# NMX-200.net
KiCad netlist of a schematic drawn in EAGLE
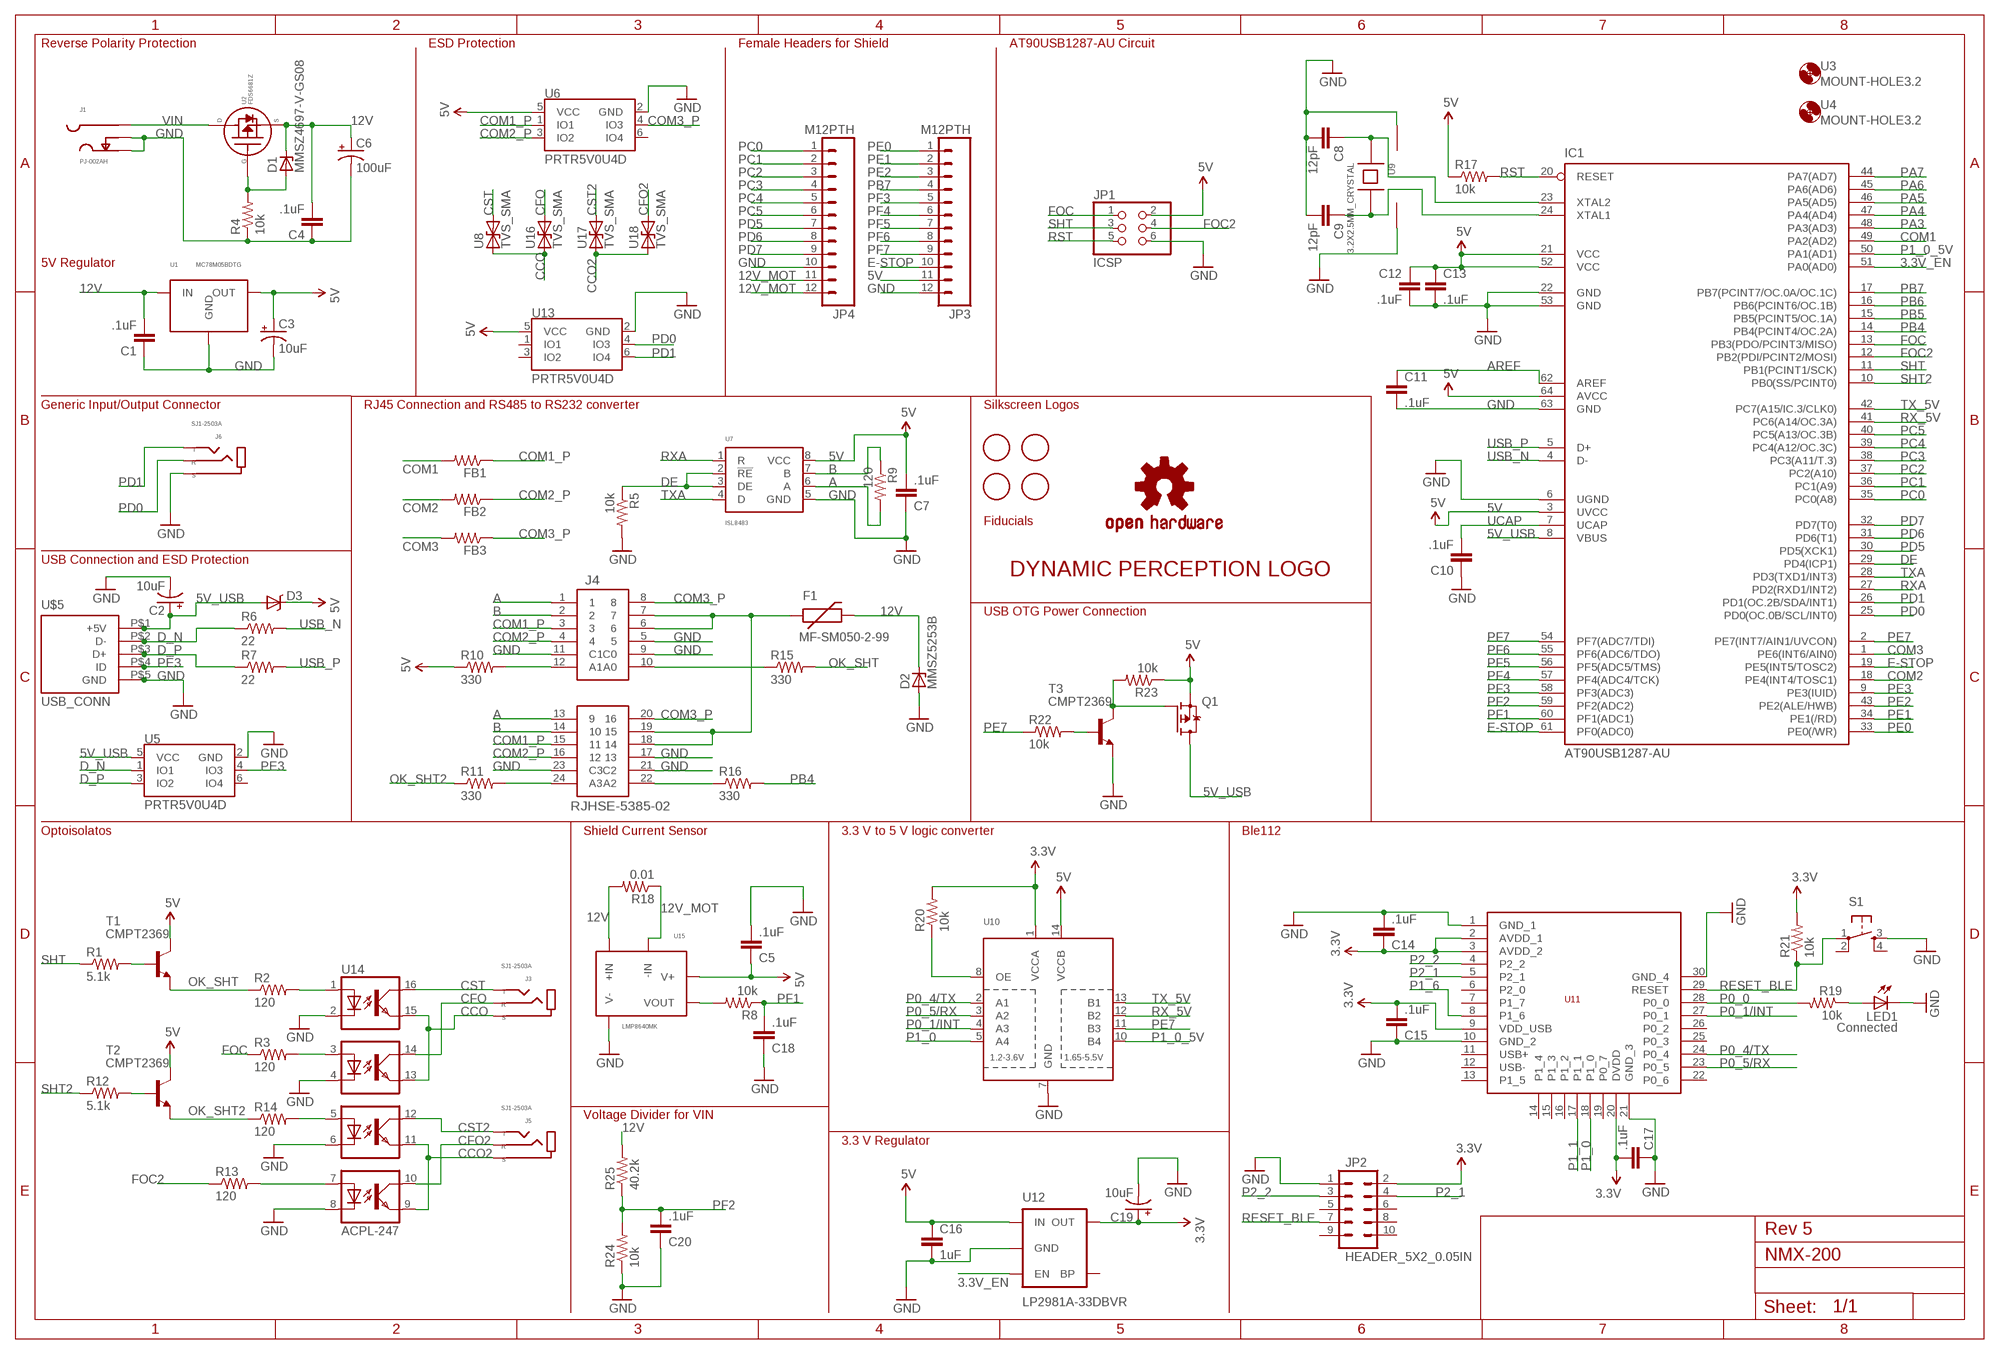
[diagram p0: schematic, sheet 1]

(export (version "E")
  (design (tool "Eeschema 10.0.6"))
  (components
    (comp (ref "C1")
      (value ".1uF")
      (footprint "eagle-import:0402-CAP")
      (fields (field (name "MF") "Taiyo Yuden") (field (name "MPN") "TMK105BJ104KV-F"))
      (libsource (lib "eagle-import") (part "CAP0402-CAP"))
    )
    (comp (ref "C2")
      (value "10uF")
      (footprint "eagle-import:EIA3216")
      (fields (field (name "MF") "Kemet") (field (name "MPN") "T491A106M016AT"))
      (libsource (lib "eagle-import") (part "CAP_POL1206"))
    )
    (comp (ref "C3")
      (value "10uF")
      (footprint "eagle-import:EIA3216")
      (fields (field (name "MF") "Kemet") (field (name "MPN") "T491A106M016AT"))
      (libsource (lib "eagle-import") (part "CAP_POL1206"))
    )
    (comp (ref "C4")
      (value ".1uF")
      (footprint "eagle-import:0402-CAP")
      (fields (field (name "MF") "Taiyo Yuden") (field (name "MPN") "TMK105BJ104KV-F"))
      (libsource (lib "eagle-import") (part "CAP0402-CAP"))
    )
    (comp (ref "C5")
      (value ".1uF")
      (footprint "eagle-import:0402-CAP")
      (fields (field (name "MF") "Taiyo Yuden") (field (name "MPN") "TMK105BJ104KV-F"))
      (libsource (lib "eagle-import") (part "CAP0402-CAP"))
    )
    (comp (ref "C6")
      (value "100uF")
      (footprint "eagle-import:PANASONIC_D")
      (fields (field (name "MF") "Panasonic Electronic Components") (field (name "MPN") "EEE-1EA101XP"))
      (libsource (lib "eagle-import") (part "CAP_POLD"))
    )
    (comp (ref "C7")
      (value ".1uF")
      (footprint "eagle-import:0402-CAP")
      (fields (field (name "MF") "Taiyo Yuden") (field (name "MPN") "TMK105BJ104KV-F"))
      (libsource (lib "eagle-import") (part "CAP0402-CAP"))
    )
    (comp (ref "C8")
      (value "12pF")
      (footprint "eagle-import:0402-CAP")
      (fields (field (name "MF") "TDK Corporation") (field (name "MPN") "C1005C0G1H120J050BA"))
      (libsource (lib "eagle-import") (part "CAP0402-CAP"))
    )
    (comp (ref "C9")
      (value "12pF")
      (footprint "eagle-import:0402-CAP")
      (fields (field (name "MF") "TDK Corporation") (field (name "MPN") "C1005C0G1H120J050BA"))
      (libsource (lib "eagle-import") (part "CAP0402-CAP"))
    )
    (comp (ref "C10")
      (value ".1uF")
      (footprint "eagle-import:0402-CAP")
      (fields (field (name "MF") "Taiyo Yuden") (field (name "MPN") "TMK105BJ104KV-F"))
      (libsource (lib "eagle-import") (part "CAP0402-CAP"))
    )
    (comp (ref "C11")
      (value ".1uF")
      (footprint "eagle-import:0402-CAP")
      (fields (field (name "MF") "Taiyo Yuden") (field (name "MPN") "TMK105BJ104KV-F"))
      (libsource (lib "eagle-import") (part "CAP0402-CAP"))
    )
    (comp (ref "C12")
      (value ".1uF")
      (footprint "eagle-import:0402-CAP")
      (fields (field (name "MF") "Taiyo Yuden") (field (name "MPN") "TMK105BJ104KV-F"))
      (libsource (lib "eagle-import") (part "CAP0402-CAP"))
    )
    (comp (ref "C13")
      (value ".1uF")
      (footprint "eagle-import:0402-CAP")
      (fields (field (name "MF") "Taiyo Yuden") (field (name "MPN") "TMK105BJ104KV-F"))
      (libsource (lib "eagle-import") (part "CAP0402-CAP"))
    )
    (comp (ref "C14")
      (value ".1uF")
      (footprint "eagle-import:0402-CAP")
      (fields (field (name "MF") "Taiyo Yuden") (field (name "MPN") "TMK105BJ104KV-F"))
      (libsource (lib "eagle-import") (part "CAP0402-CAP"))
    )
    (comp (ref "C15")
      (value ".1uF")
      (footprint "eagle-import:0402-CAP")
      (fields (field (name "MF") "Taiyo Yuden") (field (name "MPN") "TMK105BJ104KV-F"))
      (libsource (lib "eagle-import") (part "CAP0402-CAP"))
    )
    (comp (ref "C16")
      (value "1uF")
      (footprint "eagle-import:0402-CAP")
      (fields (field (name "MF") "TDK Corporation") (field (name "MPN") "C1005X5R1C105K050BC"))
      (libsource (lib "eagle-import") (part "CAP0402-CAP"))
    )
    (comp (ref "C17")
      (value ".1uF")
      (footprint "eagle-import:0402-CAP")
      (fields (field (name "MF") "Taiyo Yuden") (field (name "MPN") "TMK105BJ104KV-F"))
      (libsource (lib "eagle-import") (part "CAP0402-CAP"))
    )
    (comp (ref "C18")
      (value ".1uF")
      (footprint "eagle-import:0402-CAP")
      (fields (field (name "MF") "Taiyo Yuden") (field (name "MPN") "TMK105BJ104KV-F"))
      (libsource (lib "eagle-import") (part "CAP0402-CAP"))
    )
    (comp (ref "C19")
      (value "10uF")
      (footprint "eagle-import:EIA3216")
      (fields (field (name "MF") "Kemet") (field (name "MPN") "T491A106M016AT"))
      (libsource (lib "eagle-import") (part "CAP_POL1206"))
    )
    (comp (ref "C20")
      (value ".1uF")
      (footprint "eagle-import:0402-CAP")
      (fields (field (name "MF") "Taiyo Yuden") (field (name "MPN") "TMK105BJ104KV-F"))
      (libsource (lib "eagle-import") (part "CAP0402-CAP"))
    )
    (comp (ref "D1")
      (value "MMSZ4697-V-GS08")
      (footprint "eagle-import:SOD123")
      (fields
        (field (name "MF") "Vishay Semiconductor Diodes Division")
        (field (name "MPN") "MMSZ4697-E3-08")
      )
      (libsource (lib "eagle-import") (part "ZENER-DIODESOD123"))
    )
    (comp (ref "D2")
      (value "MMSZ5253B")
      (footprint "eagle-import:SOD123")
      (fields (field (name "MF") "Fairchild Semiconductor"))
      (libsource (lib "eagle-import") (part "ZENER-DIODESOD123"))
    )
    (comp (ref "D3")
      (value "DIODE-SCHOTTKY-BAT20J")
      (footprint "eagle-import:SOD-323")
      (fields (field (name "MF") "NXP Semiconductors") (field (name "MPN") "PMEG3010BEA,115"))
      (libsource (lib "eagle-import") (part "DIODE-SCHOTTKY-BAT20J"))
    )
    (comp (ref "F1")
      (value "MF-SM050-2-99")
      (footprint "eagle-import:PTC-2920")
      (fields (field (name "MF") "Bel Fuse") (field (name "MPN") "0ZCD0050FF2C"))
      (libsource (lib "eagle-import") (part "PTC2920"))
    )
    (comp (ref "FB1")
      (value "HZ0402B102R-10")
      (footprint "eagle-import:R0402")
      (fields (field (name "MF") "Laird-Signal Integrity Products"))
      (libsource (lib "eagle-import") (part "R-US_R0402"))
    )
    (comp (ref "FB2")
      (value "HZ0402B102R-10")
      (footprint "eagle-import:R0402")
      (fields (field (name "MF") "Laird-Signal Integrity Products"))
      (libsource (lib "eagle-import") (part "R-US_R0402"))
    )
    (comp (ref "FB3")
      (value "HZ0402B102R-10")
      (footprint "eagle-import:R0402")
      (fields (field (name "MF") "Laird-Signal Integrity Products"))
      (libsource (lib "eagle-import") (part "R-US_R0402"))
    )
    (comp (ref "FRAME2")
      (value "A3L-LOCSILK_SCREEN")
      (footprint "eagle-import:DRAWING_NAME")
      (libsource (lib "eagle-import") (part "A3L-LOCSILK_SCREEN"))
    )
    (comp (ref "IC1")
      (value "AT90USB1287-AU")
      (footprint "eagle-import:TQFP64")
      (fields (field (name "MF") "Atmel"))
      (libsource (lib "eagle-import") (part "AT90USB1287-AU"))
    )
    (comp (ref "J1")
      (value "PJ-002AH")
      (footprint "eagle-import:DC_JACK_KLDX")
      (fields (field (name "MF") "CUI Inc"))
      (libsource (lib "eagle-import") (part "DC_JACK"))
    )
    (comp (ref "J3")
      (value "SJ1-2503A")
      (footprint "eagle-import:SJ1-2503A")
      (fields (field (name "MF") "CUI Inc"))
      (libsource (lib "eagle-import") (part "TRS_JACKSJ1-2503A"))
    )
    (comp (ref "J4")
      (value "RJHSE-5385-02")
      (footprint "eagle-import:RJHSE-5385-02")
      (fields (field (name "MF") "Amphenol Commercial Products"))
      (libsource (lib "eagle-import") (part "RJ45_DOUBLEPTH"))
    )
    (comp (ref "J5")
      (value "SJ1-2503A")
      (footprint "eagle-import:SJ1-2503A")
      (fields (field (name "MF") "CUI Inc"))
      (libsource (lib "eagle-import") (part "TRS_JACKSJ1-2503A"))
    )
    (comp (ref "J6")
      (value "SJ1-2503A")
      (footprint "eagle-import:SJ1-2503A")
      (fields (field (name "MF") "CUI Inc"))
      (libsource (lib "eagle-import") (part "TRS_JACKSJ1-2503A"))
    )
    (comp (ref "JP1")
      (value "ICSP")
      (footprint "eagle-import:2X03")
      (fields (field (name "MF") "FCI") (field (name "MPN") "67996-406HLF"))
      (libsource (lib "eagle-import") (part "PINHD-2X3"))
    )
    (comp (ref "JP2")
      (value "HEADER_5X2_0.05IN")
      (footprint "eagle-import:HEADER_5X2_0.05IN")
      (fields (field (name "MF") "FCI") (field (name "MPN") "20021121-00010T4LF"))
      (libsource (lib "eagle-import") (part "HEADER_5X2_0.05IN"))
    )
    (comp (ref "JP3")
      (value "M12PTH")
      (footprint "eagle-import:1X12")
      (fields (field (name "MF") "Sullins Connector Solutions") (field (name "MPN") "PPTC121LFBN-RC"))
      (libsource (lib "eagle-import") (part "M12PTH"))
    )
    (comp (ref "JP4")
      (value "M12PTH")
      (footprint "eagle-import:1X12")
      (fields (field (name "MF") "Sullins Connector Solutions") (field (name "MPN") "PPTC121LFBN-RC"))
      (libsource (lib "eagle-import") (part "M12PTH"))
    )
    (comp (ref "LED1")
      (value "Connected")
      (footprint "eagle-import:LED-0603")
      (fields (field (name "MF") "Lite-On Inc") (field (name "MPN") "LTST-S270TBKT"))
      (libsource (lib "eagle-import") (part "LED0603"))
    )
    (comp (ref "Q1")
      (value "P-CHANNEL_MOSFET")
      (footprint "eagle-import:SOT23-3")
      (fields (field (name "MF") "Fairchild Semiconductor") (field (name "MPN") "FDV304P"))
      (libsource (lib "eagle-import") (part "P-CHANNEL_MOSFET"))
    )
    (comp (ref "R1")
      (value "5.1k")
      (footprint "eagle-import:R0402")
      (fields (field (name "MF") "Yageo") (field (name "MPN") "RC0402JR-075K1L"))
      (libsource (lib "eagle-import") (part "R-US_R0402"))
    )
    (comp (ref "R2")
      (value "120")
      (footprint "eagle-import:R0402")
      (fields (field (name "MF") "Yageo") (field (name "MPN") "RC0402FR-07180RL"))
      (libsource (lib "eagle-import") (part "R-US_R0402"))
    )
    (comp (ref "R3")
      (value "120")
      (footprint "eagle-import:R0402")
      (fields (field (name "MF") "Yageo") (field (name "MPN") "RC0402FR-07180RL"))
      (libsource (lib "eagle-import") (part "R-US_R0402"))
    )
    (comp (ref "R4")
      (value "10k")
      (footprint "eagle-import:R0402")
      (fields (field (name "MF") "Yageo") (field (name "MPN") "RC0402FR-0710KL"))
      (libsource (lib "eagle-import") (part "R-US_R0402"))
    )
    (comp (ref "R5")
      (value "10k")
      (footprint "eagle-import:R0402")
      (fields (field (name "MF") "Yageo") (field (name "MPN") "RC0402FR-0710KL"))
      (libsource (lib "eagle-import") (part "R-US_R0402"))
    )
    (comp (ref "R6")
      (value "22")
      (footprint "eagle-import:R0402")
      (fields (field (name "MF") "Yageo") (field (name "MPN") "RC0402JR-0722RL"))
      (libsource (lib "eagle-import") (part "R-US_R0402"))
    )
    (comp (ref "R7")
      (value "22")
      (footprint "eagle-import:R0402")
      (fields (field (name "MF") "Yageo") (field (name "MPN") "RC0402JR-0722RL"))
      (libsource (lib "eagle-import") (part "R-US_R0402"))
    )
    (comp (ref "R8")
      (value "10k")
      (footprint "eagle-import:R0402")
      (fields (field (name "MF") "Yageo") (field (name "MPN") "RC0402FR-0710KL"))
      (libsource (lib "eagle-import") (part "R-US_R0402"))
    )
    (comp (ref "R9")
      (value "120")
      (footprint "eagle-import:R0402")
      (fields (field (name "MF") "Yageo") (field (name "MPN") "RC0402JR-07120RL"))
      (libsource (lib "eagle-import") (part "R-US_R0402"))
    )
    (comp (ref "R10")
      (value "330")
      (footprint "eagle-import:R0402")
      (fields (field (name "MF") "Yageo") (field (name "MPN") "RC0402FR-07330RL"))
      (libsource (lib "eagle-import") (part "R-US_R0402"))
    )
    (comp (ref "R11")
      (value "330")
      (footprint "eagle-import:R0402")
      (fields (field (name "MF") "Yageo") (field (name "MPN") "RC0402FR-07330RL"))
      (libsource (lib "eagle-import") (part "R-US_R0402"))
    )
    (comp (ref "R12")
      (value "5.1k")
      (footprint "eagle-import:R0402")
      (fields (field (name "MF") "Yageo") (field (name "MPN") "RC0402JR-075K1L"))
      (libsource (lib "eagle-import") (part "R-US_R0402"))
    )
    (comp (ref "R13")
      (value "120")
      (footprint "eagle-import:R0402")
      (fields (field (name "MF") "Yageo") (field (name "MPN") "RC0402FR-07180RL"))
      (libsource (lib "eagle-import") (part "R-US_R0402"))
    )
    (comp (ref "R14")
      (value "120")
      (footprint "eagle-import:R0402")
      (fields (field (name "MF") "Yageo") (field (name "MPN") "RC0402FR-07180RL"))
      (libsource (lib "eagle-import") (part "R-US_R0402"))
    )
    (comp (ref "R15")
      (value "330")
      (footprint "eagle-import:R0402")
      (fields (field (name "MF") "Yageo") (field (name "MPN") "RC0402FR-07330RL"))
      (libsource (lib "eagle-import") (part "R-US_R0402"))
    )
    (comp (ref "R16")
      (value "330")
      (footprint "eagle-import:R0402")
      (fields (field (name "MF") "Yageo") (field (name "MPN") "RC0402FR-07330RL"))
      (libsource (lib "eagle-import") (part "R-US_R0402"))
    )
    (comp (ref "R17")
      (value "10k")
      (footprint "eagle-import:R0402")
      (fields (field (name "MF") "Yageo") (field (name "MPN") "RC0402FR-0710KL"))
      (libsource (lib "eagle-import") (part "R-US_R0402"))
    )
    (comp (ref "R18")
      (value "0.01")
      (footprint "eagle-import:R1206")
      (fields (field (name "MF") "TE Connectivity") (field (name "MPN") "RLP73V2BR010JTD"))
      (libsource (lib "eagle-import") (part "R-US_R1206"))
    )
    (comp (ref "R19")
      (value "10k")
      (footprint "eagle-import:R0402")
      (fields (field (name "MF") "Yageo") (field (name "MPN") "RC0402FR-0714KL"))
      (libsource (lib "eagle-import") (part "R-US_R0402"))
    )
    (comp (ref "R20")
      (value "10k")
      (footprint "eagle-import:R0402")
      (fields (field (name "MF") "Yageo") (field (name "MPN") "RC0402FR-0710KL"))
      (libsource (lib "eagle-import") (part "R-US_R0402"))
    )
    (comp (ref "R21")
      (value "10k")
      (footprint "eagle-import:R0402")
      (fields (field (name "MF") "Yageo") (field (name "MPN") "RC0402FR-0710KL"))
      (libsource (lib "eagle-import") (part "R-US_R0402"))
    )
    (comp (ref "R22")
      (value "10k")
      (footprint "eagle-import:R0402")
      (fields (field (name "MF") "Yageo") (field (name "MPN") "RC0402FR-0710KL"))
      (libsource (lib "eagle-import") (part "R-US_R0402"))
    )
    (comp (ref "R23")
      (value "10k")
      (footprint "eagle-import:R0402")
      (fields (field (name "MF") "Yageo") (field (name "MPN") "RC0402FR-0710KL"))
      (libsource (lib "eagle-import") (part "R-US_R0402"))
    )
    (comp (ref "R24")
      (value "10k")
      (footprint "eagle-import:R0402")
      (fields (field (name "MF") "Yageo") (field (name "MPN") "RC0402FR-0710KL"))
      (libsource (lib "eagle-import") (part "R-US_R0402"))
    )
    (comp (ref "R25")
      (value "40.2k")
      (footprint "eagle-import:R0402")
      (fields (field (name "MF") "Yageo") (field (name "MPN") "RC0402FR-0740K2L"))
      (libsource (lib "eagle-import") (part "R-US_R0402"))
    )
    (comp (ref "S1")
      (value "TAC_SWITCH")
      (footprint "eagle-import:TACTICLE_SWITCH_SMD_EVQP0_BOT")
      (fields (field (name "MF") "Panasonic Electronic Components") (field (name "MPN") "EVQ-P0Q02Q"))
      (libsource (lib "eagle-import") (part "TAC_SWITCH"))
    )
    (comp (ref "T1")
      (value "CMPT2369")
      (footprint "eagle-import:SOT23-BEC")
      (fields (field (name "MF") "Rohm Semiconductor") (field (name "MPN") "2SD1757KT146Q"))
      (libsource (lib "eagle-import") (part "-NPN-SOT23-BECBCW60"))
    )
    (comp (ref "T2")
      (value "CMPT2369")
      (footprint "eagle-import:SOT23-BEC")
      (fields (field (name "MF") "Rohm Semiconductor") (field (name "MPN") "2SD1757KT146Q"))
      (libsource (lib "eagle-import") (part "-NPN-SOT23-BECBCW60"))
    )
    (comp (ref "T3")
      (value "CMPT2369")
      (footprint "eagle-import:SOT23-BEC")
      (fields (field (name "MF") "Fairchild Semiconductor") (field (name "MPN") "BC847BMTF"))
      (libsource (lib "eagle-import") (part "-NPN-SOT23-BECBCW60"))
    )
    (comp (ref "U$1")
      (value "DP_LOGOMICRO")
      (footprint "eagle-import:DP_LOGO_MICRO")
      (libsource (lib "eagle-import") (part "DP_LOGOMICRO"))
    )
    (comp (ref "U$2")
      (value "OSHW-LOGOS")
      (footprint "eagle-import:OSHW-LOGO-S")
      (libsource (lib "eagle-import") (part "OSHW-LOGOS"))
    )
    (comp (ref "U$3")
      (value "FIDUCIAL")
      (footprint "eagle-import:FIDUCIAL_1MM")
      (libsource (lib "eagle-import") (part "FIDUCIAL"))
    )
    (comp (ref "U$4")
      (value "FIDUCIAL")
      (footprint "eagle-import:FIDUCIAL_1MM")
      (libsource (lib "eagle-import") (part "FIDUCIAL"))
    )
    (comp (ref "U$5")
      (value "USB_CONN")
      (footprint "eagle-import:10118194-0001LF")
      (libsource (lib "eagle-import") (part "USB_CONN"))
    )
    (comp (ref "U$6")
      (value "FIDUCIAL")
      (footprint "eagle-import:FIDUCIAL_1MM")
      (libsource (lib "eagle-import") (part "FIDUCIAL"))
    )
    (comp (ref "U$7")
      (value "FIDUCIAL")
      (footprint "eagle-import:FIDUCIAL_1MM")
      (libsource (lib "eagle-import") (part "FIDUCIAL"))
    )
    (comp (ref "U1")
      (value "MC78M05BDTG")
      (footprint "eagle-import:DPAK-3")
      (fields (field (name "MF") "ON Semiconductor") (field (name "MPN") "MC78M05BDTRKG"))
      (libsource (lib "eagle-import") (part "VOLTAGE_REG"))
    )
    (comp (ref "U2")
      (value "FDS6681Z")
      (footprint "eagle-import:DSO-8")
      (fields (field (name "MF") "Fairchild Semiconductor"))
      (libsource (lib "eagle-import") (part "MOSFET_P-CHANNEL"))
    )
    (comp (ref "U3")
      (value "MOUNT-HOLE3.2")
      (footprint "eagle-import:3,2")
      (libsource (lib "eagle-import") (part "MOUNT-HOLE3.2"))
    )
    (comp (ref "U4")
      (value "MOUNT-HOLE3.2")
      (footprint "eagle-import:3,2")
      (libsource (lib "eagle-import") (part "MOUNT-HOLE3.2"))
    )
    (comp (ref "U5")
      (value "PRTR5V0U4D")
      (footprint "eagle-import:SOT23-6")
      (fields (field (name "MF") "NXP Semiconductors"))
      (libsource (lib "eagle-import") (part "PRTR5V0U4D"))
    )
    (comp (ref "U6")
      (value "PRTR5V0U4D")
      (footprint "eagle-import:SOT23-6")
      (fields (field (name "MF") "NXP Semiconductors"))
      (libsource (lib "eagle-import") (part "PRTR5V0U4D"))
    )
    (comp (ref "U7")
      (value "ISL8483")
      (footprint "eagle-import:SO-08")
      (fields
        (field (name "MF") "TEXAS INSTRUMENTS")
        (field (name "MPN") "SN65176BD")
        (field (name "MF_1") "TEXAS INSTRUMENTS")
        (field (name "MPN_1") "SN65176BD")
        (field (name "OC_FARNELL") "9589970")
        (field (name "OC_NEWARK") "08F5891")
      )
      (libsource (lib "eagle-import") (part "SN65176D"))
    )
    (comp (ref "U8")
      (value "TVS_SMA")
      (footprint "eagle-import:SMA_DIODE")
      (fields (field (name "MF") "Bourns Inc") (field (name "MPN") "SMAJ48CA"))
      (libsource (lib "eagle-import") (part "TVS_SMA"))
    )
    (comp (ref "U9")
      (value "3.2X2.5MM_CRYSTAL")
      (footprint "eagle-import:3.2X2.5MM")
      (fields (field (name "MF") "AVX Corp/Kyocera Corp") (field (name "MPN") "CX3225SB16000E0FPZ25"))
      (libsource (lib "eagle-import") (part "3.2X2.5MM_CRYSTAL"))
    )
    (comp (ref "U10")
      (value "TXB0104PWR")
      (footprint "eagle-import:TSSOP14")
      (fields (field (name "MF") "Texas Instruments"))
      (libsource (lib "eagle-import") (part "TXB0104PWR"))
    )
    (comp (ref "U11")
      (value "BLE112")
      (footprint "eagle-import:BLE112-A")
      (fields (field (name "MF") "BlueGiga Technologies Inc") (field (name "MPN") "BLE112-A-V1"))
      (libsource (lib "eagle-import") (part "BLE112"))
    )
    (comp (ref "U12")
      (value "LP2981A-33DBVR")
      (footprint "eagle-import:SOT23-5")
      (fields (field (name "MF") "Texas Instruments"))
      (libsource (lib "eagle-import") (part "V_REG_LDOSMD"))
    )
    (comp (ref "U13")
      (value "PRTR5V0U4D")
      (footprint "eagle-import:SOT23-6")
      (fields (field (name "MF") "NXP Semiconductors"))
      (libsource (lib "eagle-import") (part "PRTR5V0U4D"))
    )
    (comp (ref "U14")
      (value "ACPL-247")
      (footprint "eagle-import:16-SOIC")
      (fields (field (name "MF") "Avago Technologies US Inc.") (field (name "MPN") "ACPL-247-500E"))
      (libsource (lib "eagle-import") (part "ACPL-247"))
    )
    (comp (ref "U15")
      (value "LMP8640MK")
      (footprint "eagle-import:6-SOT")
      (fields (field (name "MF") "Texas Instruments") (field (name "MPN") "LMP8640MK-H/NOPB"))
      (libsource (lib "eagle-import") (part "LMP8640MK"))
    )
    (comp (ref "U16")
      (value "TVS_SMA")
      (footprint "eagle-import:SMA_DIODE")
      (fields (field (name "MF") "Bourns Inc") (field (name "MPN") "SMAJ48CA"))
      (libsource (lib "eagle-import") (part "TVS_SMA"))
    )
    (comp (ref "U17")
      (value "TVS_SMA")
      (footprint "eagle-import:SMA_DIODE")
      (fields (field (name "MF") "Bourns Inc") (field (name "MPN") "SMAJ48CA"))
      (libsource (lib "eagle-import") (part "TVS_SMA"))
    )
    (comp (ref "U18")
      (value "TVS_SMA")
      (footprint "eagle-import:SMA_DIODE")
      (fields (field (name "MF") "Bourns Inc") (field (name "MPN") "SMAJ48CA"))
      (libsource (lib "eagle-import") (part "TVS_SMA"))
    )
  )
  (nets
    (net (code "1") (name "/3.3V_EN") (class "Default")
      (node (ref "IC1") (pin "51") (pinfunction "PA0(AD0)_51") (pintype "bidirectional"))
      (node (ref "U12") (pin "3") (pinfunction "EN_3") (pintype "input"))
    )
    (net (code "2") (name "/5V_USB") (class "Default")
      (node (ref "C2") (pin "A") (pinfunction "+_A") (pintype "passive"))
      (node (ref "D3") (pin "A") (pinfunction "A_A") (pintype "passive"))
      (node (ref "IC1") (pin "8") (pinfunction "VBUS_8") (pintype "power_in"))
      (node (ref "Q1") (pin "D") (pinfunction "D_D") (pintype "passive"))
      (node (ref "U$5") (pin "P$1") (pinfunction "+5V_P$1") (pintype "bidirectional"))
      (node (ref "U5") (pin "5") (pinfunction "VCC_5") (pintype "power_in"))
    )
    (net (code "3") (name "/12V") (class "Default")
      (node (ref "C1") (pin "2") (pinfunction "2_2") (pintype "passive"))
      (node (ref "C4") (pin "2") (pinfunction "2_2") (pintype "passive"))
      (node (ref "C6") (pin "+") (pinfunction "+_+") (pintype "passive"))
      (node (ref "D1") (pin "C") (pinfunction "C_C") (pintype "passive"))
      (node (ref "D2") (pin "C") (pinfunction "C_C") (pintype "passive"))
      (node (ref "F1") (pin "P$2") (pinfunction "2_P$2") (pintype "bidirectional"))
      (node (ref "R18") (pin "2") (pinfunction "2_2") (pintype "passive"))
      (node (ref "R25") (pin "2") (pinfunction "2_2") (pintype "passive"))
      (node (ref "U1") (pin "1") (pinfunction "IN_1") (pintype "bidirectional"))
      (node (ref "U15") (pin "3") (pinfunction "+IN_3") (pintype "bidirectional"))
      (node (ref "U2") (pin "1") (pinfunction "SOURCE_1") (pintype "bidirectional"))
      (node (ref "U2") (pin "2") (pinfunction "SOURCE_2") (pintype "bidirectional"))
      (node (ref "U2") (pin "3") (pinfunction "SOURCE_3") (pintype "bidirectional"))
    )
    (net (code "4") (name "/12V_MOT") (class "Default")
      (node (ref "JP4") (pin "11") (pinfunction "11_11") (pintype "passive"))
      (node (ref "JP4") (pin "12") (pinfunction "12_12") (pintype "passive"))
      (node (ref "R18") (pin "1") (pinfunction "1_1") (pintype "passive"))
      (node (ref "U15") (pin "4") (pinfunction "-IN_4") (pintype "bidirectional"))
    )
    (net (code "5") (name "/A") (class "Default")
      (node (ref "J4") (pin "1") (pinfunction "1_1") (pintype "bidirectional"))
      (node (ref "J4") (pin "13") (pinfunction "9_13") (pintype "bidirectional"))
      (node (ref "R9") (pin "2") (pinfunction "2_2") (pintype "passive"))
      (node (ref "U7") (pin "6") (pinfunction "A_6") (pintype "input"))
    )
    (net (code "6") (name "/AREF") (class "Default")
      (node (ref "C11") (pin "1") (pinfunction "1_1") (pintype "passive"))
      (node (ref "IC1") (pin "62") (pinfunction "AREF_62") (pintype "bidirectional"))
    )
    (net (code "7") (name "/B") (class "Default")
      (node (ref "J4") (pin "14") (pinfunction "10_14") (pintype "bidirectional"))
      (node (ref "J4") (pin "2") (pinfunction "2_2") (pintype "bidirectional"))
      (node (ref "R9") (pin "1") (pinfunction "1_1") (pintype "passive"))
      (node (ref "U7") (pin "7") (pinfunction "B_7") (pintype "input"))
    )
    (net (code "8") (name "/CCO") (class "Default")
      (node (ref "J3") (pin "1") (pinfunction "S_1") (pintype "bidirectional"))
      (node (ref "U14") (pin "13") (pinfunction "13_13") (pintype "passive"))
      (node (ref "U14") (pin "15") (pinfunction "15_15") (pintype "passive"))
      (node (ref "U16") (pin "C") (pinfunction "1_C") (pintype "passive"))
      (node (ref "U8") (pin "C") (pinfunction "1_C") (pintype "passive"))
    )
    (net (code "9") (name "/CCO2") (class "Default")
      (node (ref "J5") (pin "1") (pinfunction "S_1") (pintype "bidirectional"))
      (node (ref "U14") (pin "11") (pinfunction "11_11") (pintype "passive"))
      (node (ref "U14") (pin "9") (pinfunction "9_9") (pintype "passive"))
      (node (ref "U17") (pin "C") (pinfunction "1_C") (pintype "passive"))
      (node (ref "U18") (pin "C") (pinfunction "1_C") (pintype "passive"))
    )
    (net (code "10") (name "/CFO") (class "Default")
      (node (ref "J3") (pin "4") (pinfunction "R_4") (pintype "bidirectional"))
      (node (ref "U14") (pin "14") (pinfunction "14_14") (pintype "passive"))
      (node (ref "U16") (pin "A") (pinfunction "2_A") (pintype "passive"))
    )
    (net (code "11") (name "/CFO2") (class "Default")
      (node (ref "J5") (pin "4") (pinfunction "R_4") (pintype "bidirectional"))
      (node (ref "U14") (pin "10") (pinfunction "10_10") (pintype "passive"))
      (node (ref "U18") (pin "A") (pinfunction "2_A") (pintype "passive"))
    )
    (net (code "12") (name "/COM1") (class "Default")
      (node (ref "FB1") (pin "2") (pinfunction "2_2") (pintype "passive"))
      (node (ref "IC1") (pin "49") (pinfunction "PA2(AD2)_49") (pintype "bidirectional"))
    )
    (net (code "13") (name "/COM1_P") (class "Default")
      (node (ref "FB1") (pin "1") (pinfunction "1_1") (pintype "passive"))
      (node (ref "J4") (pin "15") (pinfunction "11_15") (pintype "bidirectional"))
      (node (ref "J4") (pin "3") (pinfunction "3_3") (pintype "bidirectional"))
      (node (ref "U6") (pin "1") (pinfunction "IO1_1") (pintype "bidirectional"))
    )
    (net (code "14") (name "/COM2") (class "Default")
      (node (ref "FB2") (pin "2") (pinfunction "2_2") (pintype "passive"))
      (node (ref "IC1") (pin "18") (pinfunction "PE4(INT4/TOSC1)_18") (pintype "bidirectional"))
    )
    (net (code "15") (name "/COM2_P") (class "Default")
      (node (ref "FB2") (pin "1") (pinfunction "1_1") (pintype "passive"))
      (node (ref "J4") (pin "16") (pinfunction "12_16") (pintype "bidirectional"))
      (node (ref "J4") (pin "4") (pinfunction "4_4") (pintype "bidirectional"))
      (node (ref "U6") (pin "3") (pinfunction "IO2_3") (pintype "bidirectional"))
    )
    (net (code "16") (name "/COM3") (class "Default")
      (node (ref "FB3") (pin "2") (pinfunction "2_2") (pintype "passive"))
      (node (ref "IC1") (pin "1") (pinfunction "PE6(INT6/AIN0)_1") (pintype "bidirectional"))
    )
    (net (code "17") (name "/COM3_P") (class "Default")
      (node (ref "FB3") (pin "1") (pinfunction "1_1") (pintype "passive"))
      (node (ref "J4") (pin "20") (pinfunction "16_20") (pintype "bidirectional"))
      (node (ref "J4") (pin "8") (pinfunction "8_8") (pintype "bidirectional"))
      (node (ref "U6") (pin "4") (pinfunction "IO3_4") (pintype "bidirectional"))
    )
    (net (code "18") (name "/CST") (class "Default")
      (node (ref "J3") (pin "2") (pinfunction "T_2") (pintype "bidirectional"))
      (node (ref "J3") (pin "3") (pinfunction "T_3") (pintype "bidirectional"))
      (node (ref "U14") (pin "16") (pinfunction "16_16") (pintype "passive"))
      (node (ref "U8") (pin "A") (pinfunction "2_A") (pintype "passive"))
    )
    (net (code "19") (name "/CST2") (class "Default")
      (node (ref "J5") (pin "2") (pinfunction "T_2") (pintype "bidirectional"))
      (node (ref "J5") (pin "3") (pinfunction "T_3") (pintype "bidirectional"))
      (node (ref "U14") (pin "12") (pinfunction "12_12") (pintype "passive"))
      (node (ref "U17") (pin "A") (pinfunction "2_A") (pintype "passive"))
    )
    (net (code "20") (name "/DE") (class "Default")
      (node (ref "IC1") (pin "29") (pinfunction "PD4(ICP1)_29") (pintype "bidirectional"))
      (node (ref "R5") (pin "1") (pinfunction "1_1") (pintype "passive"))
      (node (ref "U7") (pin "2") (pinfunction "~{RE}_2") (pintype "input"))
      (node (ref "U7") (pin "3") (pinfunction "DE_3") (pintype "input"))
    )
    (net (code "21") (name "/D_N") (class "Default")
      (node (ref "R6") (pin "1") (pinfunction "1_1") (pintype "passive"))
      (node (ref "U$5") (pin "P$2") (pinfunction "D-_P$2") (pintype "bidirectional"))
      (node (ref "U5") (pin "1") (pinfunction "IO1_1") (pintype "bidirectional"))
    )
    (net (code "22") (name "/D_P") (class "Default")
      (node (ref "R7") (pin "1") (pinfunction "1_1") (pintype "passive"))
      (node (ref "U$5") (pin "P$3") (pinfunction "D+_P$3") (pintype "bidirectional"))
      (node (ref "U5") (pin "3") (pinfunction "IO2_3") (pintype "bidirectional"))
    )
    (net (code "23") (name "/E-STOP") (class "Default")
      (node (ref "IC1") (pin "19") (pinfunction "PE5(INT5/TOSC2)_19") (pintype "bidirectional"))
      (node (ref "IC1") (pin "61") (pinfunction "PF0(ADC0)_61") (pintype "bidirectional"))
      (node (ref "JP3") (pin "10") (pinfunction "10_10") (pintype "passive"))
    )
    (net (code "24") (name "/FOC") (class "Default")
      (node (ref "IC1") (pin "13") (pinfunction "PB3(PDO/PCINT3/MISO)_13") (pintype "bidirectional"))
      (node (ref "JP1") (pin "1") (pinfunction "1_1") (pintype "passive"))
      (node (ref "R3") (pin "1") (pinfunction "1_1") (pintype "passive"))
    )
    (net (code "25") (name "/FOC2") (class "Default")
      (node (ref "IC1") (pin "12") (pinfunction "PB2(PDI/PCINT2/MOSI)_12") (pintype "bidirectional"))
      (node (ref "JP1") (pin "4") (pinfunction "4_4") (pintype "passive"))
      (node (ref "R13") (pin "1") (pinfunction "1_1") (pintype "passive"))
    )
    (net (code "26") (name "/OK_SHT") (class "Default")
      (node (ref "R15") (pin "2") (pinfunction "2_2") (pintype "passive"))
      (node (ref "R2") (pin "1") (pinfunction "1_1") (pintype "passive"))
      (node (ref "T1") (pin "E") (pinfunction "E_E") (pintype "passive"))
    )
    (net (code "27") (name "/OK_SHT2") (class "Default")
      (node (ref "R11") (pin "1") (pinfunction "1_1") (pintype "passive"))
      (node (ref "R14") (pin "1") (pinfunction "1_1") (pintype "passive"))
      (node (ref "T2") (pin "E") (pinfunction "E_E") (pintype "passive"))
    )
    (net (code "28") (name "/P0_0") (class "Default")
      (node (ref "R19") (pin "2") (pinfunction "2_2") (pintype "passive"))
      (node (ref "U11") (pin "28") (pinfunction "P0_0_28") (pintype "bidirectional"))
    )
    (net (code "29") (name "/P0_1{slash}INT") (class "Default")
      (node (ref "U10") (pin "4") (pinfunction "A3_4") (pintype "bidirectional"))
      (node (ref "U11") (pin "27") (pinfunction "P0_1_27") (pintype "bidirectional"))
    )
    (net (code "30") (name "/P0_4{slash}TX") (class "Default")
      (node (ref "U10") (pin "2") (pinfunction "A1_2") (pintype "bidirectional"))
      (node (ref "U11") (pin "24") (pinfunction "P0_4_24") (pintype "bidirectional"))
    )
    (net (code "31") (name "/P0_5{slash}RX") (class "Default")
      (node (ref "U10") (pin "3") (pinfunction "A2_3") (pintype "bidirectional"))
      (node (ref "U11") (pin "23") (pinfunction "P0_5_23") (pintype "bidirectional"))
    )
    (net (code "32") (name "/P1_0") (class "Default")
      (node (ref "U10") (pin "5") (pinfunction "A4_5") (pintype "bidirectional"))
      (node (ref "U11") (pin "18") (pinfunction "P1_0_18") (pintype "bidirectional"))
    )
    (net (code "33") (name "/P1_0_5V") (class "Default")
      (node (ref "IC1") (pin "50") (pinfunction "PA1(AD1)_50") (pintype "bidirectional"))
      (node (ref "U10") (pin "10") (pinfunction "B4_10") (pintype "bidirectional"))
    )
    (net (code "34") (name "/P1_1") (class "Default")
      (node (ref "U11") (pin "17") (pinfunction "P1_1_17") (pintype "bidirectional"))
    )
    (net (code "35") (name "/P1_6") (class "Default")
      (node (ref "U11") (pin "8") (pinfunction "P1_6_8") (pintype "bidirectional"))
    )
    (net (code "36") (name "/P2_1") (class "Default")
      (node (ref "JP2") (pin "4") (pinfunction "4_4") (pintype "passive"))
      (node (ref "U11") (pin "5") (pinfunction "P2_1_5") (pintype "bidirectional"))
    )
    (net (code "37") (name "/P2_2") (class "Default")
      (node (ref "JP2") (pin "3") (pinfunction "3_3") (pintype "passive"))
      (node (ref "U11") (pin "4") (pinfunction "P2_2_4") (pintype "bidirectional"))
    )
    (net (code "38") (name "/PA3") (class "Default")
      (node (ref "IC1") (pin "48") (pinfunction "PA3(AD3)_48") (pintype "bidirectional"))
    )
    (net (code "39") (name "/PA4") (class "Default")
      (node (ref "IC1") (pin "47") (pinfunction "PA4(AD4)_47") (pintype "bidirectional"))
    )
    (net (code "40") (name "/PA5") (class "Default")
      (node (ref "IC1") (pin "46") (pinfunction "PA5(AD5)_46") (pintype "bidirectional"))
    )
    (net (code "41") (name "/PA6") (class "Default")
      (node (ref "IC1") (pin "45") (pinfunction "PA6(AD6)_45") (pintype "bidirectional"))
    )
    (net (code "42") (name "/PA7") (class "Default")
      (node (ref "IC1") (pin "44") (pinfunction "PA7(AD7)_44") (pintype "bidirectional"))
    )
    (net (code "43") (name "/PB4") (class "Default")
      (node (ref "IC1") (pin "14") (pinfunction "PB4(PCINT4/OC.2A)_14") (pintype "bidirectional"))
      (node (ref "R16") (pin "2") (pinfunction "2_2") (pintype "passive"))
    )
    (net (code "44") (name "/PB5") (class "Default")
      (node (ref "IC1") (pin "15") (pinfunction "PB5(PCINT5/OC.1A)_15") (pintype "bidirectional"))
    )
    (net (code "45") (name "/PB6") (class "Default")
      (node (ref "IC1") (pin "16") (pinfunction "PB6(PCINT6/OC.1B)_16") (pintype "bidirectional"))
    )
    (net (code "46") (name "/PB7") (class "Default")
      (node (ref "IC1") (pin "17") (pinfunction "PB7(PCINT7/OC.0A/OC.1C)_17") (pintype "bidirectional"))
      (node (ref "JP3") (pin "4") (pinfunction "4_4") (pintype "passive"))
    )
    (net (code "47") (name "/PC0") (class "Default")
      (node (ref "IC1") (pin "35") (pinfunction "PC0(A8)_35") (pintype "bidirectional"))
      (node (ref "JP4") (pin "1") (pinfunction "1_1") (pintype "passive"))
    )
    (net (code "48") (name "/PC1") (class "Default")
      (node (ref "IC1") (pin "36") (pinfunction "PC1(A9)_36") (pintype "bidirectional"))
      (node (ref "JP4") (pin "2") (pinfunction "2_2") (pintype "passive"))
    )
    (net (code "49") (name "/PC2") (class "Default")
      (node (ref "IC1") (pin "37") (pinfunction "PC2(A10)_37") (pintype "bidirectional"))
      (node (ref "JP4") (pin "3") (pinfunction "3_3") (pintype "passive"))
    )
    (net (code "50") (name "/PC3") (class "Default")
      (node (ref "IC1") (pin "38") (pinfunction "PC3(A11/T.3)_38") (pintype "bidirectional"))
      (node (ref "JP4") (pin "4") (pinfunction "4_4") (pintype "passive"))
    )
    (net (code "51") (name "/PC4") (class "Default")
      (node (ref "IC1") (pin "39") (pinfunction "PC4(A12/OC.3C)_39") (pintype "bidirectional"))
      (node (ref "JP4") (pin "5") (pinfunction "5_5") (pintype "passive"))
    )
    (net (code "52") (name "/PC5") (class "Default")
      (node (ref "IC1") (pin "40") (pinfunction "PC5(A13/OC.3B)_40") (pintype "bidirectional"))
      (node (ref "JP4") (pin "6") (pinfunction "6_6") (pintype "passive"))
    )
    (net (code "53") (name "/PD0") (class "Default")
      (node (ref "IC1") (pin "25") (pinfunction "PD0(OC.0B/SCL/INT0)_25") (pintype "bidirectional"))
      (node (ref "J6") (pin "4") (pinfunction "R_4") (pintype "bidirectional"))
      (node (ref "U13") (pin "4") (pinfunction "IO3_4") (pintype "bidirectional"))
    )
    (net (code "54") (name "/PD1") (class "Default")
      (node (ref "IC1") (pin "26") (pinfunction "PD1(OC.2B/SDA/INT1)_26") (pintype "bidirectional"))
      (node (ref "J6") (pin "2") (pinfunction "T_2") (pintype "bidirectional"))
      (node (ref "J6") (pin "3") (pinfunction "T_3") (pintype "bidirectional"))
      (node (ref "U13") (pin "6") (pinfunction "IO4_6") (pintype "bidirectional"))
    )
    (net (code "55") (name "/PD5") (class "Default")
      (node (ref "IC1") (pin "30") (pinfunction "PD5(XCK1)_30") (pintype "bidirectional"))
      (node (ref "JP4") (pin "7") (pinfunction "7_7") (pintype "passive"))
    )
    (net (code "56") (name "/PD6") (class "Default")
      (node (ref "IC1") (pin "31") (pinfunction "PD6(T1)_31") (pintype "bidirectional"))
      (node (ref "JP4") (pin "8") (pinfunction "8_8") (pintype "passive"))
    )
    (net (code "57") (name "/PD7") (class "Default")
      (node (ref "IC1") (pin "32") (pinfunction "PD7(T0)_32") (pintype "bidirectional"))
      (node (ref "JP4") (pin "9") (pinfunction "9_9") (pintype "passive"))
    )
    (net (code "58") (name "/PE0") (class "Default")
      (node (ref "IC1") (pin "33") (pinfunction "PE0(/WR)_33") (pintype "bidirectional"))
      (node (ref "JP3") (pin "1") (pinfunction "1_1") (pintype "passive"))
    )
    (net (code "59") (name "/PE1") (class "Default")
      (node (ref "IC1") (pin "34") (pinfunction "PE1(/RD)_34") (pintype "bidirectional"))
      (node (ref "JP3") (pin "2") (pinfunction "2_2") (pintype "passive"))
    )
    (net (code "60") (name "/PE2") (class "Default")
      (node (ref "IC1") (pin "43") (pinfunction "PE2(ALE/HWB)_43") (pintype "bidirectional"))
      (node (ref "JP3") (pin "3") (pinfunction "3_3") (pintype "passive"))
    )
    (net (code "61") (name "/PE3") (class "Default")
      (node (ref "IC1") (pin "9") (pinfunction "PE3(IUID)_9") (pintype "bidirectional"))
      (node (ref "U$5") (pin "P$4") (pinfunction "ID_P$4") (pintype "bidirectional"))
      (node (ref "U5") (pin "4") (pinfunction "IO3_4") (pintype "bidirectional"))
    )
    (net (code "62") (name "/PE7") (class "Default")
      (node (ref "IC1") (pin "2") (pinfunction "PE7(INT7/AIN1/UVCON)_2") (pintype "bidirectional"))
      (node (ref "R22") (pin "1") (pinfunction "1_1") (pintype "passive"))
      (node (ref "U10") (pin "11") (pinfunction "B3_11") (pintype "bidirectional"))
    )
    (net (code "63") (name "/PF1") (class "Default")
      (node (ref "C18") (pin "2") (pinfunction "2_2") (pintype "passive"))
      (node (ref "IC1") (pin "60") (pinfunction "PF1(ADC1)_60") (pintype "bidirectional"))
      (node (ref "R8") (pin "1") (pinfunction "1_1") (pintype "passive"))
    )
    (net (code "64") (name "/PF2") (class "Default")
      (node (ref "C20") (pin "2") (pinfunction "2_2") (pintype "passive"))
      (node (ref "IC1") (pin "59") (pinfunction "PF2(ADC2)_59") (pintype "bidirectional"))
      (node (ref "R24") (pin "2") (pinfunction "2_2") (pintype "passive"))
      (node (ref "R25") (pin "1") (pinfunction "1_1") (pintype "passive"))
    )
    (net (code "65") (name "/PF3") (class "Default")
      (node (ref "IC1") (pin "58") (pinfunction "PF3(ADC3)_58") (pintype "bidirectional"))
      (node (ref "JP3") (pin "5") (pinfunction "5_5") (pintype "passive"))
    )
    (net (code "66") (name "/PF4") (class "Default")
      (node (ref "IC1") (pin "57") (pinfunction "PF4(ADC4/TCK)_57") (pintype "bidirectional"))
      (node (ref "JP3") (pin "6") (pinfunction "6_6") (pintype "passive"))
    )
    (net (code "67") (name "/PF5") (class "Default")
      (node (ref "IC1") (pin "56") (pinfunction "PF5(ADC5/TMS)_56") (pintype "bidirectional"))
      (node (ref "JP3") (pin "7") (pinfunction "7_7") (pintype "passive"))
    )
    (net (code "68") (name "/PF6") (class "Default")
      (node (ref "IC1") (pin "55") (pinfunction "PF6(ADC6/TDO)_55") (pintype "bidirectional"))
      (node (ref "JP3") (pin "8") (pinfunction "8_8") (pintype "passive"))
    )
    (net (code "69") (name "/PF7") (class "Default")
      (node (ref "IC1") (pin "54") (pinfunction "PF7(ADC7/TDI)_54") (pintype "bidirectional"))
      (node (ref "JP3") (pin "9") (pinfunction "9_9") (pintype "passive"))
    )
    (net (code "70") (name "/RESET_BLE") (class "Default")
      (node (ref "JP2") (pin "7") (pinfunction "7_7") (pintype "passive"))
      (node (ref "R21") (pin "1") (pinfunction "1_1") (pintype "passive"))
      (node (ref "S1") (pin "1") (pinfunction "1_1") (pintype "passive"))
      (node (ref "U11") (pin "29") (pinfunction "RESET_29") (pintype "input"))
    )
    (net (code "71") (name "/RST") (class "Default")
      (node (ref "IC1") (pin "20") (pinfunction "RESET_20") (pintype "input"))
      (node (ref "JP1") (pin "5") (pinfunction "5_5") (pintype "passive"))
      (node (ref "R17") (pin "2") (pinfunction "2_2") (pintype "passive"))
    )
    (net (code "72") (name "/RXA") (class "Default")
      (node (ref "IC1") (pin "27") (pinfunction "PD2(RXD1/INT2)_27") (pintype "bidirectional"))
      (node (ref "U7") (pin "1") (pinfunction "R_1") (pintype "input"))
    )
    (net (code "73") (name "/RX_5V") (class "Default")
      (node (ref "IC1") (pin "41") (pinfunction "PC6(A14/OC.3A)_41") (pintype "bidirectional"))
      (node (ref "U10") (pin "12") (pinfunction "B2_12") (pintype "bidirectional"))
    )
    (net (code "74") (name "/SHT") (class "Default")
      (node (ref "IC1") (pin "11") (pinfunction "PB1(PCINT1/SCK)_11") (pintype "bidirectional"))
      (node (ref "JP1") (pin "3") (pinfunction "3_3") (pintype "passive"))
      (node (ref "R1") (pin "1") (pinfunction "1_1") (pintype "passive"))
    )
    (net (code "75") (name "/SHT2") (class "Default")
      (node (ref "IC1") (pin "10") (pinfunction "PB0(SS/PCINT0)_10") (pintype "bidirectional"))
      (node (ref "R12") (pin "1") (pinfunction "1_1") (pintype "passive"))
    )
    (net (code "76") (name "/TXA") (class "Default")
      (node (ref "IC1") (pin "28") (pinfunction "PD3(TXD1/INT3)_28") (pintype "bidirectional"))
      (node (ref "U7") (pin "4") (pinfunction "D_4") (pintype "input"))
    )
    (net (code "77") (name "/TX_5V") (class "Default")
      (node (ref "IC1") (pin "42") (pinfunction "PC7(A15/IC.3/CLK0)_42") (pintype "bidirectional"))
      (node (ref "U10") (pin "13") (pinfunction "B1_13") (pintype "bidirectional"))
    )
    (net (code "78") (name "/UCAP") (class "Default")
      (node (ref "C10") (pin "2") (pinfunction "2_2") (pintype "passive"))
      (node (ref "IC1") (pin "7") (pinfunction "UCAP_7") (pintype "power_in"))
    )
    (net (code "79") (name "/USB_N") (class "Default")
      (node (ref "IC1") (pin "4") (pinfunction "D-_4") (pintype "bidirectional"))
      (node (ref "R6") (pin "2") (pinfunction "2_2") (pintype "passive"))
    )
    (net (code "80") (name "/USB_P") (class "Default")
      (node (ref "IC1") (pin "5") (pinfunction "D+_5") (pintype "bidirectional"))
      (node (ref "R7") (pin "2") (pinfunction "2_2") (pintype "passive"))
    )
    (net (code "81") (name "/VIN") (class "Default")
      (node (ref "J1") (pin "PWR") (pinfunction "PIN_PWR") (pintype "bidirectional"))
      (node (ref "U2") (pin "5") (pinfunction "DRAIN_5") (pintype "bidirectional"))
      (node (ref "U2") (pin "6") (pinfunction "DRAIN_6") (pintype "bidirectional"))
      (node (ref "U2") (pin "7") (pinfunction "DRAIN_7") (pintype "bidirectional"))
      (node (ref "U2") (pin "8") (pinfunction "DRAIN_8") (pintype "bidirectional"))
    )
    (net (code "82") (name "3.3V") (class "Default")
      (node (ref "C14") (pin "1") (pinfunction "1_1") (pintype "passive"))
      (node (ref "C15") (pin "2") (pinfunction "2_2") (pintype "passive"))
      (node (ref "C17") (pin "2") (pinfunction "2_2") (pintype "passive"))
      (node (ref "C19") (pin "A") (pinfunction "+_A") (pintype "passive"))
      (node (ref "JP2") (pin "2") (pinfunction "2_2") (pintype "passive"))
      (node (ref "R20") (pin "2") (pinfunction "2_2") (pintype "passive"))
      (node (ref "R21") (pin "2") (pinfunction "2_2") (pintype "passive"))
      (node (ref "U10") (pin "1") (pinfunction "VCCA_1") (pintype "bidirectional"))
      (node (ref "U11") (pin "2") (pinfunction "AVDD_1_2") (pintype "power_in"))
      (node (ref "U11") (pin "20") (pinfunction "DVDD_20") (pintype "power_in"))
      (node (ref "U11") (pin "3") (pinfunction "AVDD_2_3") (pintype "power_in"))
      (node (ref "U11") (pin "9") (pinfunction "VDD_USB_9") (pintype "power_in"))
      (node (ref "U12") (pin "5") (pinfunction "OUT_5") (pintype "passive"))
    )
    (net (code "83") (name "5V") (class "Default")
      (node (ref "C12") (pin "1") (pinfunction "1_1") (pintype "passive"))
      (node (ref "C13") (pin "1") (pinfunction "1_1") (pintype "passive"))
      (node (ref "C16") (pin "1") (pinfunction "1_1") (pintype "passive"))
      (node (ref "C3") (pin "A") (pinfunction "+_A") (pintype "passive"))
      (node (ref "C5") (pin "1") (pinfunction "1_1") (pintype "passive"))
      (node (ref "C7") (pin "2") (pinfunction "2_2") (pintype "passive"))
      (node (ref "D3") (pin "C") (pinfunction "C_C") (pintype "passive"))
      (node (ref "IC1") (pin "21") (pinfunction "VCC_21") (pintype "power_in"))
      (node (ref "IC1") (pin "3") (pinfunction "UVCC_3") (pintype "power_in"))
      (node (ref "IC1") (pin "52") (pinfunction "VCC_52") (pintype "power_in"))
      (node (ref "IC1") (pin "64") (pinfunction "AVCC_64") (pintype "bidirectional"))
      (node (ref "JP1") (pin "2") (pinfunction "2_2") (pintype "passive"))
      (node (ref "JP3") (pin "11") (pinfunction "11_11") (pintype "passive"))
      (node (ref "Q1") (pin "S") (pinfunction "S_S") (pintype "passive"))
      (node (ref "R10") (pin "1") (pinfunction "1_1") (pintype "passive"))
      (node (ref "R17") (pin "1") (pinfunction "1_1") (pintype "passive"))
      (node (ref "R23") (pin "1") (pinfunction "1_1") (pintype "passive"))
      (node (ref "T1") (pin "C") (pinfunction "C_C") (pintype "passive"))
      (node (ref "T2") (pin "C") (pinfunction "C_C") (pintype "passive"))
      (node (ref "U1") (pin "2") (pinfunction "OUT_2") (pintype "bidirectional"))
      (node (ref "U10") (pin "14") (pinfunction "VCCB_14") (pintype "bidirectional"))
      (node (ref "U12") (pin "1") (pinfunction "IN_1") (pintype "input"))
      (node (ref "U13") (pin "5") (pinfunction "VCC_5") (pintype "power_in"))
      (node (ref "U15") (pin "6") (pinfunction "V+_6") (pintype "bidirectional"))
      (node (ref "U6") (pin "5") (pinfunction "VCC_5") (pintype "power_in"))
      (node (ref "U7") (pin "8") (pinfunction "VCC_8") (pintype "input"))
    )
    (net (code "84") (name "GND") (class "Default")
      (node (ref "C1") (pin "1") (pinfunction "1_1") (pintype "passive"))
      (node (ref "C10") (pin "1") (pinfunction "1_1") (pintype "passive"))
      (node (ref "C11") (pin "2") (pinfunction "2_2") (pintype "passive"))
      (node (ref "C12") (pin "2") (pinfunction "2_2") (pintype "passive"))
      (node (ref "C13") (pin "2") (pinfunction "2_2") (pintype "passive"))
      (node (ref "C14") (pin "2") (pinfunction "2_2") (pintype "passive"))
      (node (ref "C15") (pin "1") (pinfunction "1_1") (pintype "passive"))
      (node (ref "C16") (pin "2") (pinfunction "2_2") (pintype "passive"))
      (node (ref "C17") (pin "1") (pinfunction "1_1") (pintype "passive"))
      (node (ref "C18") (pin "1") (pinfunction "1_1") (pintype "passive"))
      (node (ref "C19") (pin "C") (pinfunction "-_C") (pintype "passive"))
      (node (ref "C2") (pin "C") (pinfunction "-_C") (pintype "passive"))
      (node (ref "C20") (pin "1") (pinfunction "1_1") (pintype "passive"))
      (node (ref "C3") (pin "C") (pinfunction "-_C") (pintype "passive"))
      (node (ref "C4") (pin "1") (pinfunction "1_1") (pintype "passive"))
      (node (ref "C5") (pin "2") (pinfunction "2_2") (pintype "passive"))
      (node (ref "C6") (pin "-") (pinfunction "-_-") (pintype "passive"))
      (node (ref "C7") (pin "1") (pinfunction "1_1") (pintype "passive"))
      (node (ref "C8") (pin "2") (pinfunction "2_2") (pintype "passive"))
      (node (ref "C9") (pin "2") (pinfunction "2_2") (pintype "passive"))
      (node (ref "D2") (pin "A") (pinfunction "A_A") (pintype "passive"))
      (node (ref "IC1") (pin "22") (pinfunction "GND_22") (pintype "power_in"))
      (node (ref "IC1") (pin "53") (pinfunction "GND_53") (pintype "power_in"))
      (node (ref "IC1") (pin "6") (pinfunction "UGND_6") (pintype "power_in"))
      (node (ref "IC1") (pin "63") (pinfunction "GND_63") (pintype "power_in"))
      (node (ref "J1") (pin "GND") (pinfunction "SLEEVE_GND") (pintype "bidirectional"))
      (node (ref "J1") (pin "GNDBREAK") (pinfunction "SLEEVE_SHUNT_GNDBREAK") (pintype "bidirectional"))
      (node (ref "J4") (pin "11") (pinfunction "C1_11") (pintype "bidirectional"))
      (node (ref "J4") (pin "17") (pinfunction "13_17") (pintype "bidirectional"))
      (node (ref "J4") (pin "21") (pinfunction "C2_21") (pintype "bidirectional"))
      (node (ref "J4") (pin "23") (pinfunction "C3_23") (pintype "bidirectional"))
      (node (ref "J4") (pin "5") (pinfunction "5_5") (pintype "bidirectional"))
      (node (ref "J4") (pin "9") (pinfunction "C0_9") (pintype "bidirectional"))
      (node (ref "J6") (pin "1") (pinfunction "S_1") (pintype "bidirectional"))
      (node (ref "JP1") (pin "6") (pinfunction "6_6") (pintype "passive"))
      (node (ref "JP2") (pin "1") (pinfunction "1_1") (pintype "passive"))
      (node (ref "JP3") (pin "12") (pinfunction "12_12") (pintype "passive"))
      (node (ref "JP4") (pin "10") (pinfunction "10_10") (pintype "passive"))
      (node (ref "LED1") (pin "C") (pinfunction "C_C") (pintype "passive"))
      (node (ref "R24") (pin "1") (pinfunction "1_1") (pintype "passive"))
      (node (ref "R4") (pin "1") (pinfunction "1_1") (pintype "passive"))
      (node (ref "R5") (pin "2") (pinfunction "2_2") (pintype "passive"))
      (node (ref "S1") (pin "3") (pinfunction "3_3") (pintype "passive"))
      (node (ref "T3") (pin "E") (pinfunction "E_E") (pintype "passive"))
      (node (ref "U$5") (pin "P$5") (pinfunction "GND_P$5") (pintype "bidirectional"))
      (node (ref "U1") (pin "4") (pinfunction "GND_4") (pintype "bidirectional"))
      (node (ref "U10") (pin "7") (pinfunction "GND_7") (pintype "bidirectional"))
      (node (ref "U11") (pin "1") (pinfunction "GND_1_1") (pintype "power_in"))
      (node (ref "U11") (pin "10") (pinfunction "GND_2_10") (pintype "power_in"))
      (node (ref "U11") (pin "21") (pinfunction "GND_3_21") (pintype "power_in"))
      (node (ref "U11") (pin "30") (pinfunction "GND_4_30") (pintype "power_in"))
      (node (ref "U12") (pin "2") (pinfunction "GND_2") (pintype "input"))
      (node (ref "U13") (pin "2") (pinfunction "GND_2") (pintype "power_in"))
      (node (ref "U14") (pin "2") (pinfunction "2_2") (pintype "passive"))
      (node (ref "U14") (pin "4") (pinfunction "4_4") (pintype "passive"))
      (node (ref "U14") (pin "6") (pinfunction "6_6") (pintype "passive"))
      (node (ref "U14") (pin "8") (pinfunction "8_8") (pintype "passive"))
      (node (ref "U15") (pin "2") (pinfunction "V-_2") (pintype "bidirectional"))
      (node (ref "U5") (pin "2") (pinfunction "GND_2") (pintype "power_in"))
      (node (ref "U6") (pin "2") (pinfunction "GND_2") (pintype "power_in"))
      (node (ref "U7") (pin "5") (pinfunction "GND_5") (pintype "input"))
      (node (ref "U9") (pin "2") (pinfunction "GND_2") (pintype "power_in"))
      (node (ref "U9") (pin "4") (pinfunction "4_4") (pintype "power_in"))
    )
    (net (code "85") (name "Net-(F1-1)") (class "Default")
      (node (ref "F1") (pin "P$1") (pinfunction "1_P$1") (pintype "bidirectional"))
      (node (ref "J4") (pin "18") (pinfunction "14_18") (pintype "bidirectional"))
      (node (ref "J4") (pin "19") (pinfunction "15_19") (pintype "bidirectional"))
      (node (ref "J4") (pin "6") (pinfunction "6_6") (pintype "bidirectional"))
      (node (ref "J4") (pin "7") (pinfunction "7_7") (pintype "bidirectional"))
    )
    (net (code "86") (name "Net-(IC1-XTAL1)") (class "Default")
      (node (ref "C9") (pin "1") (pinfunction "1_1") (pintype "passive"))
      (node (ref "IC1") (pin "24") (pinfunction "XTAL1_24") (pintype "bidirectional"))
      (node (ref "U9") (pin "3") (pinfunction "3_3") (pintype "bidirectional"))
    )
    (net (code "87") (name "Net-(IC1-XTAL2)") (class "Default")
      (node (ref "C8") (pin "1") (pinfunction "1_1") (pintype "passive"))
      (node (ref "IC1") (pin "23") (pinfunction "XTAL2_23") (pintype "bidirectional"))
      (node (ref "U9") (pin "1") (pinfunction "1_1") (pintype "bidirectional"))
    )
    (net (code "88") (name "Net-(J4-A0)") (class "Default")
      (node (ref "J4") (pin "10") (pinfunction "A0_10") (pintype "bidirectional"))
      (node (ref "R15") (pin "1") (pinfunction "1_1") (pintype "passive"))
    )
    (net (code "89") (name "Net-(J4-A1)") (class "Default")
      (node (ref "J4") (pin "12") (pinfunction "A1_12") (pintype "bidirectional"))
      (node (ref "R10") (pin "2") (pinfunction "2_2") (pintype "passive"))
    )
    (net (code "90") (name "Net-(J4-A2)") (class "Default")
      (node (ref "J4") (pin "22") (pinfunction "A2_22") (pintype "bidirectional"))
      (node (ref "R16") (pin "1") (pinfunction "1_1") (pintype "passive"))
    )
    (net (code "91") (name "Net-(J4-A3)") (class "Default")
      (node (ref "J4") (pin "24") (pinfunction "A3_24") (pintype "bidirectional"))
      (node (ref "R11") (pin "2") (pinfunction "2_2") (pintype "passive"))
    )
    (net (code "92") (name "Net-(LED1-PadA)") (class "Default")
      (node (ref "LED1") (pin "A") (pinfunction "A_A") (pintype "passive"))
      (node (ref "R19") (pin "1") (pinfunction "1_1") (pintype "passive"))
    )
    (net (code "93") (name "Net-(Q1-PadG)") (class "Default")
      (node (ref "Q1") (pin "G") (pinfunction "G_G") (pintype "passive"))
      (node (ref "R23") (pin "2") (pinfunction "2_2") (pintype "passive"))
      (node (ref "T3") (pin "C") (pinfunction "C_C") (pintype "passive"))
    )
    (net (code "94") (name "Net-(R1-Pad2)") (class "Default")
      (node (ref "R1") (pin "2") (pinfunction "2_2") (pintype "passive"))
      (node (ref "T1") (pin "B") (pinfunction "B_B") (pintype "passive"))
    )
    (net (code "95") (name "Net-(R2-Pad2)") (class "Default")
      (node (ref "R2") (pin "2") (pinfunction "2_2") (pintype "passive"))
      (node (ref "U14") (pin "1") (pinfunction "1_1") (pintype "passive"))
    )
    (net (code "96") (name "Net-(R3-Pad2)") (class "Default")
      (node (ref "R3") (pin "2") (pinfunction "2_2") (pintype "passive"))
      (node (ref "U14") (pin "3") (pinfunction "3_3") (pintype "passive"))
    )
    (net (code "97") (name "Net-(R12-Pad2)") (class "Default")
      (node (ref "R12") (pin "2") (pinfunction "2_2") (pintype "passive"))
      (node (ref "T2") (pin "B") (pinfunction "B_B") (pintype "passive"))
    )
    (net (code "98") (name "Net-(R13-Pad2)") (class "Default")
      (node (ref "R13") (pin "2") (pinfunction "2_2") (pintype "passive"))
      (node (ref "U14") (pin "7") (pinfunction "7_7") (pintype "passive"))
    )
    (net (code "99") (name "Net-(R14-Pad2)") (class "Default")
      (node (ref "R14") (pin "2") (pinfunction "2_2") (pintype "passive"))
      (node (ref "U14") (pin "5") (pinfunction "5_5") (pintype "passive"))
    )
    (net (code "100") (name "Net-(R22-Pad2)") (class "Default")
      (node (ref "R22") (pin "2") (pinfunction "2_2") (pintype "passive"))
      (node (ref "T3") (pin "B") (pinfunction "B_B") (pintype "passive"))
    )
    (net (code "101") (name "Net-(U2-GATE)") (class "Default")
      (node (ref "D1") (pin "A") (pinfunction "A_A") (pintype "passive"))
      (node (ref "R4") (pin "2") (pinfunction "2_2") (pintype "passive"))
      (node (ref "U2") (pin "4") (pinfunction "GATE_4") (pintype "bidirectional"))
    )
    (net (code "102") (name "Net-(U10-OE)") (class "Default")
      (node (ref "R20") (pin "1") (pinfunction "1_1") (pintype "passive"))
      (node (ref "U10") (pin "8") (pinfunction "OE_8") (pintype "bidirectional"))
    )
    (net (code "103") (name "Net-(U15-VOUT)") (class "Default")
      (node (ref "R8") (pin "2") (pinfunction "2_2") (pintype "passive"))
      (node (ref "U15") (pin "1") (pinfunction "VOUT_1") (pintype "bidirectional"))
    )
    (net (code "104") (name "unconnected-(JP2-Pad5)") (class "Default")
      (node (ref "JP2") (pin "5") (pinfunction "5_5") (pintype "passive"))
    )
    (net (code "105") (name "unconnected-(JP2-Pad6)") (class "Default")
      (node (ref "JP2") (pin "6") (pinfunction "6_6") (pintype "passive"))
    )
    (net (code "106") (name "unconnected-(JP2-Pad8)") (class "Default")
      (node (ref "JP2") (pin "8") (pinfunction "8_8") (pintype "passive"))
    )
    (net (code "107") (name "unconnected-(JP2-Pad9)") (class "Default")
      (node (ref "JP2") (pin "9") (pinfunction "9_9") (pintype "passive"))
    )
    (net (code "108") (name "unconnected-(JP2-Pad10)") (class "Default")
      (node (ref "JP2") (pin "10") (pinfunction "10_10") (pintype "passive"))
    )
    (net (code "109") (name "unconnected-(S1-Pad2)") (class "Default")
      (node (ref "S1") (pin "2") (pinfunction "2_2") (pintype "passive"))
    )
    (net (code "110") (name "unconnected-(S1-Pad4)") (class "Default")
      (node (ref "S1") (pin "4") (pinfunction "4_4") (pintype "passive"))
    )
    (net (code "111") (name "unconnected-(U5-IO4-Pad6)") (class "Default")
      (node (ref "U5") (pin "6") (pinfunction "IO4_6") (pintype "bidirectional"))
    )
    (net (code "112") (name "unconnected-(U6-IO4-Pad6)") (class "Default")
      (node (ref "U6") (pin "6") (pinfunction "IO4_6") (pintype "bidirectional"))
    )
    (net (code "113") (name "unconnected-(U11-P0_2-Pad26)") (class "Default")
      (node (ref "U11") (pin "26") (pinfunction "P0_2_26") (pintype "bidirectional"))
    )
    (net (code "114") (name "unconnected-(U11-P0_3-Pad25)") (class "Default")
      (node (ref "U11") (pin "25") (pinfunction "P0_3_25") (pintype "bidirectional"))
    )
    (net (code "115") (name "unconnected-(U11-P0_6-Pad22)") (class "Default")
      (node (ref "U11") (pin "22") (pinfunction "P0_6_22") (pintype "bidirectional"))
    )
    (net (code "116") (name "unconnected-(U11-P0_7-Pad19)") (class "Default")
      (node (ref "U11") (pin "19") (pinfunction "P0_7_19") (pintype "bidirectional"))
    )
    (net (code "117") (name "unconnected-(U11-P1_2-Pad16)") (class "Default")
      (node (ref "U11") (pin "16") (pinfunction "P1_2_16") (pintype "bidirectional"))
    )
    (net (code "118") (name "unconnected-(U11-P1_3-Pad15)") (class "Default")
      (node (ref "U11") (pin "15") (pinfunction "P1_3_15") (pintype "bidirectional"))
    )
    (net (code "119") (name "unconnected-(U11-P1_4-Pad14)") (class "Default")
      (node (ref "U11") (pin "14") (pinfunction "P1_4_14") (pintype "bidirectional"))
    )
    (net (code "120") (name "unconnected-(U11-P1_5-Pad13)") (class "Default")
      (node (ref "U11") (pin "13") (pinfunction "P1_5_13") (pintype "bidirectional"))
    )
    (net (code "121") (name "unconnected-(U11-P1_7-Pad7)") (class "Default")
      (node (ref "U11") (pin "7") (pinfunction "P1_7_7") (pintype "bidirectional"))
    )
    (net (code "122") (name "unconnected-(U11-P2_0-Pad6)") (class "Default")
      (node (ref "U11") (pin "6") (pinfunction "P2_0_6") (pintype "bidirectional"))
    )
    (net (code "123") (name "unconnected-(U11-USB+-Pad11)") (class "Default")
      (node (ref "U11") (pin "11") (pinfunction "USB+_11") (pintype "bidirectional"))
    )
    (net (code "124") (name "unconnected-(U11-USB--Pad12)") (class "Default")
      (node (ref "U11") (pin "12") (pinfunction "USB-_12") (pintype "bidirectional"))
    )
    (net (code "125") (name "unconnected-(U12-BP-Pad4)") (class "Default")
      (node (ref "U12") (pin "4") (pinfunction "BP_4") (pintype "input"))
    )
    (net (code "126") (name "unconnected-(U13-IO1-Pad1)") (class "Default")
      (node (ref "U13") (pin "1") (pinfunction "IO1_1") (pintype "bidirectional"))
    )
    (net (code "127") (name "unconnected-(U13-IO2-Pad3)") (class "Default")
      (node (ref "U13") (pin "3") (pinfunction "IO2_3") (pintype "bidirectional"))
    )
  )
)
